# led.net
KiCad netlist of a schematic drawn in EAGLE
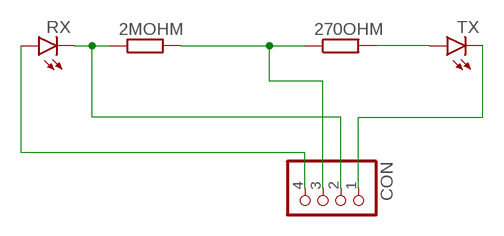
[diagram p0: schematic, sheet 1]

(export (version "E")
  (design (tool "Eeschema 10.0.6"))
  (components
    (comp (ref "2MOHM")
      (value "R-EU_0207/7")
      (footprint "eagle-import:0207_7")
      (libsource (lib "eagle-import") (part "R-EU_0207/7"))
    )
    (comp (ref "270OHM")
      (value "R-EU_0207/7")
      (footprint "eagle-import:0207_7")
      (libsource (lib "eagle-import") (part "R-EU_0207/7"))
    )
    (comp (ref "CON")
      (value "PINHD-1X4")
      (footprint "eagle-import:1X04")
      (libsource (lib "eagle-import") (part "PINHD-1X4"))
    )
    (comp (ref "RX")
      (value "LED5MM")
      (footprint "eagle-import:LED5MM")
      (libsource (lib "eagle-import") (part "LED5MM"))
    )
    (comp (ref "TX")
      (value "LED5MM")
      (footprint "eagle-import:LED5MM")
      (libsource (lib "eagle-import") (part "LED5MM"))
    )
  )
  (nets
    (net (code "1") (name "Net-(270OHM-Pad1)") (class "Default")
      (node (ref "270OHM") (pin "1") (pinfunction "1_1") (pintype "passive"))
      (node (ref "2MOHM") (pin "2") (pinfunction "2_2") (pintype "passive"))
      (node (ref "CON") (pin "3") (pinfunction "3_3") (pintype "passive"))
    )
    (net (code "2") (name "Net-(270OHM-Pad2)") (class "Default")
      (node (ref "270OHM") (pin "2") (pinfunction "2_2") (pintype "passive"))
      (node (ref "TX") (pin "A") (pinfunction "A_A") (pintype "passive"))
    )
    (net (code "3") (name "Net-(CON-Pad4)") (class "Default")
      (node (ref "CON") (pin "4") (pinfunction "4_4") (pintype "passive"))
      (node (ref "RX") (pin "A") (pinfunction "A_A") (pintype "passive"))
    )
    (net (code "4") (name "Net-(RX-C)") (class "Default")
      (node (ref "2MOHM") (pin "1") (pinfunction "1_1") (pintype "passive"))
      (node (ref "CON") (pin "2") (pinfunction "2_2") (pintype "passive"))
      (node (ref "RX") (pin "K") (pinfunction "C_K") (pintype "passive"))
    )
    (net (code "5") (name "Net-(TX-C)") (class "Default")
      (node (ref "CON") (pin "1") (pinfunction "1_1") (pintype "passive"))
      (node (ref "TX") (pin "K") (pinfunction "C_K") (pintype "passive"))
    )
  )
)
